# Adafuit_10DOF.net
KiCad netlist of a schematic drawn in EAGLE
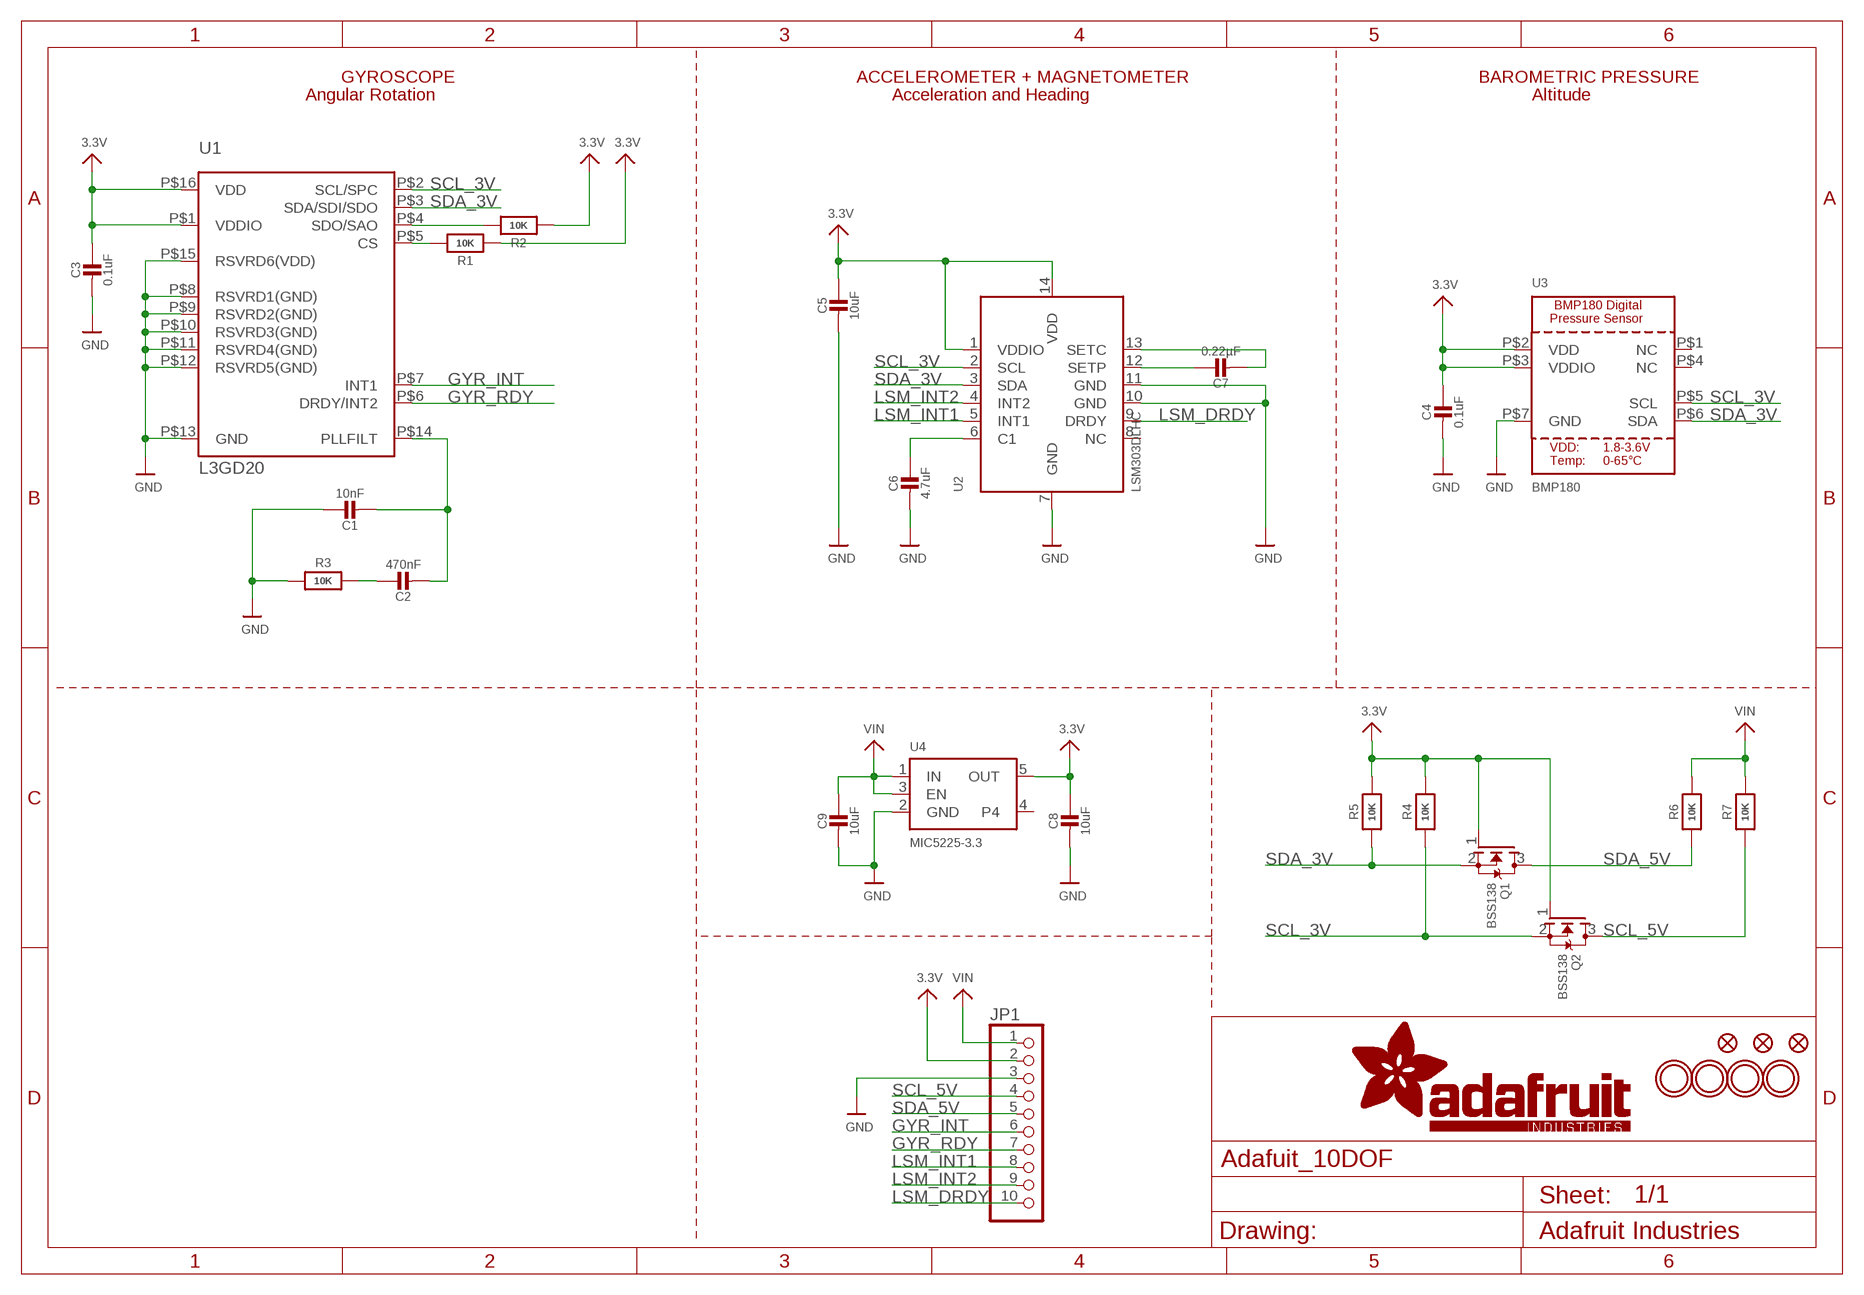
[diagram p0: schematic, sheet 1]

(export (version "E")
  (design (tool "Eeschema 10.0.6"))
  (components
    (comp (ref "C1")
      (value "10nF")
      (footprint "eagle-import:_0805MP")
      (libsource (lib "eagle-import") (part "CAP_CERAMIC_0805MP"))
    )
    (comp (ref "C2")
      (value "470nF")
      (footprint "eagle-import:_0805MP")
      (libsource (lib "eagle-import") (part "CAP_CERAMIC_0805MP"))
    )
    (comp (ref "C3")
      (value "0.1uF")
      (footprint "eagle-import:_0805MP")
      (libsource (lib "eagle-import") (part "CAP_CERAMIC_0805MP"))
    )
    (comp (ref "C4")
      (value "0.1uF")
      (footprint "eagle-import:_0805MP")
      (libsource (lib "eagle-import") (part "CAP_CERAMIC_0805MP"))
    )
    (comp (ref "C5")
      (value "10uF")
      (footprint "eagle-import:_0805MP")
      (libsource (lib "eagle-import") (part "CAP_CERAMIC_0805MP"))
    )
    (comp (ref "C6")
      (value "4.7uF")
      (footprint "eagle-import:_0805MP")
      (libsource (lib "eagle-import") (part "CAP_CERAMIC_0805MP"))
    )
    (comp (ref "C7")
      (value "0.22µF")
      (footprint "eagle-import:_0805MP")
      (libsource (lib "eagle-import") (part "CAP_CERAMIC_0805MP"))
    )
    (comp (ref "C8")
      (value "10uF")
      (footprint "eagle-import:_0805MP")
      (libsource (lib "eagle-import") (part "CAP_CERAMIC_0805MP"))
    )
    (comp (ref "C9")
      (value "10uF")
      (footprint "eagle-import:_0805MP")
      (libsource (lib "eagle-import") (part "CAP_CERAMIC_0805MP"))
    )
    (comp (ref "FID1")
      (value "FIDUCIAL\"\"")
      (footprint "eagle-import:FIDUCIAL_1MM")
      (libsource (lib "eagle-import") (part "FIDUCIAL{dblquote}{dblquote}"))
    )
    (comp (ref "FID2")
      (value "FIDUCIAL\"\"")
      (footprint "eagle-import:FIDUCIAL_1MM")
      (libsource (lib "eagle-import") (part "FIDUCIAL{dblquote}{dblquote}"))
    )
    (comp (ref "FID3")
      (value "FIDUCIAL\"\"")
      (footprint "eagle-import:FIDUCIAL_1MM")
      (libsource (lib "eagle-import") (part "FIDUCIAL{dblquote}{dblquote}"))
    )
    (comp (ref "JP1")
      (value "HEADER-1X10ROUND")
      (footprint "eagle-import:1X10_ROUND")
      (libsource (lib "eagle-import") (part "HEADER-1X10ROUND"))
    )
    (comp (ref "Q1")
      (value "BSS138")
      (footprint "eagle-import:SOT23-WIDE")
      (libsource (lib "eagle-import") (part "MOSFET-NWIDE"))
    )
    (comp (ref "Q2")
      (value "BSS138")
      (footprint "eagle-import:SOT23-WIDE")
      (libsource (lib "eagle-import") (part "MOSFET-NWIDE"))
    )
    (comp (ref "R1")
      (value "10K")
      (footprint "eagle-import:_0805MP")
      (libsource (lib "eagle-import") (part "RESISTOR_0805MP"))
    )
    (comp (ref "R2")
      (value "10K")
      (footprint "eagle-import:_0805MP")
      (libsource (lib "eagle-import") (part "RESISTOR_0805MP"))
    )
    (comp (ref "R3")
      (value "10K")
      (footprint "eagle-import:_0805MP")
      (libsource (lib "eagle-import") (part "RESISTOR_0805MP"))
    )
    (comp (ref "R4")
      (value "10K")
      (footprint "eagle-import:_0805MP")
      (libsource (lib "eagle-import") (part "RESISTOR_0805MP"))
    )
    (comp (ref "R5")
      (value "10K")
      (footprint "eagle-import:_0805MP")
      (libsource (lib "eagle-import") (part "RESISTOR_0805MP"))
    )
    (comp (ref "R6")
      (value "10K")
      (footprint "eagle-import:_0805MP")
      (libsource (lib "eagle-import") (part "RESISTOR_0805MP"))
    )
    (comp (ref "R7")
      (value "10K")
      (footprint "eagle-import:_0805MP")
      (libsource (lib "eagle-import") (part "RESISTOR_0805MP"))
    )
    (comp (ref "U$28")
      (value "MOUNTINGHOLE2.5_THICK")
      (footprint "eagle-import:MOUNTINGHOLE_2.5_PLATED_THICK")
      (libsource (lib "eagle-import") (part "MOUNTINGHOLE2.5_THICK"))
    )
    (comp (ref "U$29")
      (value "MOUNTINGHOLE2.5_THICK")
      (footprint "eagle-import:MOUNTINGHOLE_2.5_PLATED_THICK")
      (libsource (lib "eagle-import") (part "MOUNTINGHOLE2.5_THICK"))
    )
    (comp (ref "U$30")
      (value "MOUNTINGHOLE2.5_THICK")
      (footprint "eagle-import:MOUNTINGHOLE_2.5_PLATED_THICK")
      (libsource (lib "eagle-import") (part "MOUNTINGHOLE2.5_THICK"))
    )
    (comp (ref "U$31")
      (value "MOUNTINGHOLE2.5_THICK")
      (footprint "eagle-import:MOUNTINGHOLE_2.5_PLATED_THICK")
      (libsource (lib "eagle-import") (part "MOUNTINGHOLE2.5_THICK"))
    )
    (comp (ref "U1")
      (value "L3GD20")
      (footprint "eagle-import:L3G4200D_LGA16L")
      (libsource (lib "eagle-import") (part "GYRO_L3G2400D"))
    )
    (comp (ref "U2")
      (value "LSM303DLHC")
      (footprint "eagle-import:LGA14")
      (libsource (lib "eagle-import") (part "LSM303DLHC"))
    )
    (comp (ref "U3")
      (value "BMP180")
      (footprint "eagle-import:BMP180_EXTENDED")
      (libsource (lib "eagle-import") (part "BMP180EXT"))
    )
    (comp (ref "U4")
      (value "MIC5225-3.3")
      (footprint "eagle-import:SOT23-5")
      (libsource (lib "eagle-import") (part "VREG_SOT23-5"))
    )
  )
  (nets
    (net (code "1") (name "/GYR_INT") (class "Default")
      (node (ref "JP1") (pin "6") (pinfunction "6_6") (pintype "passive"))
      (node (ref "U1") (pin "P$7") (pinfunction "INT1_P$7") (pintype "bidirectional"))
    )
    (net (code "2") (name "/GYR_RDY") (class "Default")
      (node (ref "JP1") (pin "7") (pinfunction "7_7") (pintype "passive"))
      (node (ref "U1") (pin "P$6") (pinfunction "DRDY/INT2_P$6") (pintype "bidirectional"))
    )
    (net (code "3") (name "/LSM_DRDY") (class "Default")
      (node (ref "JP1") (pin "10") (pinfunction "10_10") (pintype "passive"))
      (node (ref "U2") (pin "9") (pinfunction "DRDY_9") (pintype "output"))
    )
    (net (code "4") (name "/LSM_INT1") (class "Default")
      (node (ref "JP1") (pin "8") (pinfunction "8_8") (pintype "passive"))
      (node (ref "U2") (pin "5") (pinfunction "INT1_5") (pintype "output"))
    )
    (net (code "5") (name "/LSM_INT2") (class "Default")
      (node (ref "JP1") (pin "9") (pinfunction "9_9") (pintype "passive"))
      (node (ref "U2") (pin "4") (pinfunction "INT2_4") (pintype "output"))
    )
    (net (code "6") (name "/SCL_3V") (class "Default")
      (node (ref "Q2") (pin "2") (pinfunction "S_2") (pintype "bidirectional"))
      (node (ref "R4") (pin "1") (pinfunction "1_1") (pintype "passive"))
      (node (ref "U1") (pin "P$2") (pinfunction "SCL/SPC_P$2") (pintype "bidirectional"))
      (node (ref "U2") (pin "2") (pinfunction "SCL_2") (pintype "bidirectional"))
      (node (ref "U3") (pin "P$5") (pinfunction "SCL_P$5") (pintype "bidirectional"))
    )
    (net (code "7") (name "/SCL_5V") (class "Default")
      (node (ref "JP1") (pin "4") (pinfunction "4_4") (pintype "passive"))
      (node (ref "Q2") (pin "3") (pinfunction "D_3") (pintype "bidirectional"))
      (node (ref "R7") (pin "1") (pinfunction "1_1") (pintype "passive"))
    )
    (net (code "8") (name "/SDA_3V") (class "Default")
      (node (ref "Q1") (pin "2") (pinfunction "S_2") (pintype "bidirectional"))
      (node (ref "R5") (pin "1") (pinfunction "1_1") (pintype "passive"))
      (node (ref "U1") (pin "P$3") (pinfunction "SDA/SDI/SDO_P$3") (pintype "bidirectional"))
      (node (ref "U2") (pin "3") (pinfunction "SDA_3") (pintype "bidirectional"))
      (node (ref "U3") (pin "P$6") (pinfunction "SDA_P$6") (pintype "bidirectional"))
    )
    (net (code "9") (name "/SDA_5V") (class "Default")
      (node (ref "JP1") (pin "5") (pinfunction "5_5") (pintype "passive"))
      (node (ref "Q1") (pin "3") (pinfunction "D_3") (pintype "bidirectional"))
      (node (ref "R6") (pin "1") (pinfunction "1_1") (pintype "passive"))
    )
    (net (code "10") (name "3.3V") (class "Default")
      (node (ref "C3") (pin "1") (pinfunction "1_1") (pintype "passive"))
      (node (ref "C4") (pin "1") (pinfunction "1_1") (pintype "passive"))
      (node (ref "C5") (pin "1") (pinfunction "1_1") (pintype "passive"))
      (node (ref "C8") (pin "1") (pinfunction "1_1") (pintype "passive"))
      (node (ref "JP1") (pin "2") (pinfunction "2_2") (pintype "passive"))
      (node (ref "Q1") (pin "1") (pinfunction "G_1") (pintype "bidirectional"))
      (node (ref "Q2") (pin "1") (pinfunction "G_1") (pintype "bidirectional"))
      (node (ref "R1") (pin "1") (pinfunction "1_1") (pintype "passive"))
      (node (ref "R2") (pin "1") (pinfunction "1_1") (pintype "passive"))
      (node (ref "R4") (pin "2") (pinfunction "2_2") (pintype "passive"))
      (node (ref "R5") (pin "2") (pinfunction "2_2") (pintype "passive"))
      (node (ref "U1") (pin "P$1") (pinfunction "VDDIO_P$1") (pintype "power_in"))
      (node (ref "U1") (pin "P$16") (pinfunction "VDD_P$16") (pintype "bidirectional"))
      (node (ref "U2") (pin "1") (pinfunction "VDDIO_1") (pintype "power_in"))
      (node (ref "U2") (pin "14") (pinfunction "VDD_14") (pintype "power_in"))
      (node (ref "U3") (pin "P$2") (pinfunction "VDD_P$2") (pintype "power_in"))
      (node (ref "U3") (pin "P$3") (pinfunction "VDDIO_P$3") (pintype "power_in"))
      (node (ref "U4") (pin "5") (pinfunction "OUT_5") (pintype "power_in"))
    )
    (net (code "11") (name "GND") (class "Default")
      (node (ref "C1") (pin "1") (pinfunction "1_1") (pintype "passive"))
      (node (ref "C3") (pin "2") (pinfunction "2_2") (pintype "passive"))
      (node (ref "C4") (pin "2") (pinfunction "2_2") (pintype "passive"))
      (node (ref "C5") (pin "2") (pinfunction "2_2") (pintype "passive"))
      (node (ref "C6") (pin "2") (pinfunction "2_2") (pintype "passive"))
      (node (ref "C8") (pin "2") (pinfunction "2_2") (pintype "passive"))
      (node (ref "C9") (pin "2") (pinfunction "2_2") (pintype "passive"))
      (node (ref "JP1") (pin "3") (pinfunction "3_3") (pintype "passive"))
      (node (ref "R3") (pin "1") (pinfunction "1_1") (pintype "passive"))
      (node (ref "U1") (pin "P$10") (pinfunction "RSVRD3(GND)_P$10") (pintype "bidirectional"))
      (node (ref "U1") (pin "P$11") (pinfunction "RSVRD4(GND)_P$11") (pintype "bidirectional"))
      (node (ref "U1") (pin "P$12") (pinfunction "RSVRD5(GND)_P$12") (pintype "bidirectional"))
      (node (ref "U1") (pin "P$13") (pinfunction "GND_P$13") (pintype "bidirectional"))
      (node (ref "U1") (pin "P$15") (pinfunction "RSVRD6(VDD)_P$15") (pintype "bidirectional"))
      (node (ref "U1") (pin "P$8") (pinfunction "RSVRD1(GND)_P$8") (pintype "bidirectional"))
      (node (ref "U1") (pin "P$9") (pinfunction "RSVRD2(GND)_P$9") (pintype "bidirectional"))
      (node (ref "U2") (pin "10") (pinfunction "GND_10") (pintype "power_in"))
      (node (ref "U2") (pin "11") (pinfunction "GND_11") (pintype "power_in"))
      (node (ref "U2") (pin "7") (pinfunction "GND_7") (pintype "power_in"))
      (node (ref "U3") (pin "P$7") (pinfunction "GND_P$7") (pintype "power_in"))
      (node (ref "U4") (pin "2") (pinfunction "GND_2") (pintype "power_in"))
    )
    (net (code "12") (name "Net-(C2-Pad1)") (class "Default")
      (node (ref "C2") (pin "1") (pinfunction "1_1") (pintype "passive"))
      (node (ref "R3") (pin "2") (pinfunction "2_2") (pintype "passive"))
    )
    (net (code "13") (name "Net-(U1-CS)") (class "Default")
      (node (ref "R1") (pin "2") (pinfunction "2_2") (pintype "passive"))
      (node (ref "U1") (pin "P$5") (pinfunction "CS_P$5") (pintype "bidirectional"))
    )
    (net (code "14") (name "Net-(U1-PLLFILT)") (class "Default")
      (node (ref "C1") (pin "2") (pinfunction "2_2") (pintype "passive"))
      (node (ref "C2") (pin "2") (pinfunction "2_2") (pintype "passive"))
      (node (ref "U1") (pin "P$14") (pinfunction "PLLFILT_P$14") (pintype "bidirectional"))
    )
    (net (code "15") (name "Net-(U1-SDO{slash}SAO)") (class "Default")
      (node (ref "R2") (pin "2") (pinfunction "2_2") (pintype "passive"))
      (node (ref "U1") (pin "P$4") (pinfunction "SDO/SAO_P$4") (pintype "bidirectional"))
    )
    (net (code "16") (name "Net-(U2-C1)") (class "Default")
      (node (ref "C6") (pin "1") (pinfunction "1_1") (pintype "passive"))
      (node (ref "U2") (pin "6") (pinfunction "C1_6") (pintype "bidirectional"))
    )
    (net (code "17") (name "Net-(U2-SETC)") (class "Default")
      (node (ref "C7") (pin "2") (pinfunction "2_2") (pintype "passive"))
      (node (ref "U2") (pin "13") (pinfunction "SETC_13") (pintype "bidirectional"))
    )
    (net (code "18") (name "Net-(U2-SETP)") (class "Default")
      (node (ref "C7") (pin "1") (pinfunction "1_1") (pintype "passive"))
      (node (ref "U2") (pin "12") (pinfunction "SETP_12") (pintype "bidirectional"))
    )
    (net (code "19") (name "VIN") (class "Default")
      (node (ref "C9") (pin "1") (pinfunction "1_1") (pintype "passive"))
      (node (ref "JP1") (pin "1") (pinfunction "1_1") (pintype "passive"))
      (node (ref "R6") (pin "2") (pinfunction "2_2") (pintype "passive"))
      (node (ref "R7") (pin "2") (pinfunction "2_2") (pintype "passive"))
      (node (ref "U4") (pin "1") (pinfunction "IN_1") (pintype "power_in"))
      (node (ref "U4") (pin "3") (pinfunction "EN_3") (pintype "input"))
    )
    (net (code "20") (name "unconnected-(U2-NC-Pad8)") (class "Default")
      (node (ref "U2") (pin "8") (pinfunction "NC_8") (pintype "bidirectional"))
    )
    (net (code "21") (name "unconnected-(U3-NC-PadP$1)") (class "Default")
      (node (ref "U3") (pin "P$1") (pinfunction "NC_P$1") (pintype "no_connect"))
    )
    (net (code "22") (name "unconnected-(U3-NC-PadP$4)") (class "Default")
      (node (ref "U3") (pin "P$4") (pinfunction "NC_P$4") (pintype "no_connect"))
    )
    (net (code "23") (name "unconnected-(U4-P4-Pad4)") (class "Default")
      (node (ref "U4") (pin "4") (pinfunction "P4_4") (pintype "bidirectional"))
    )
  )
)
